# 3_Interface1.net
KiCad netlist of a schematic drawn in Altium Designer
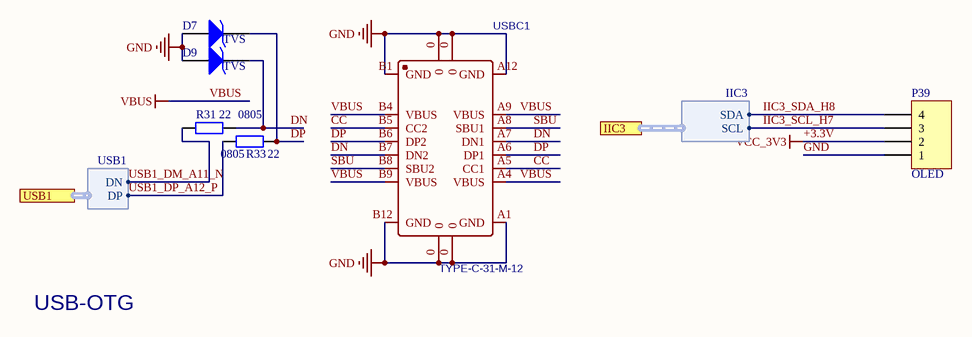
[diagram p0: 3.Interface1.SchDoc]

(export (version "E")
  (design (tool "Eeschema 10.0.6"))
  (components
    (comp (ref "D7")
      (value "TVS")
      (footprint "SOD-523")
      (description "High Conductance Fast Diode")
      (fields (field (name "PUBLISHER") "Altium Limited"))
      (libsource (lib "QT") (part "D"))
    )
    (comp (ref "D9")
      (value "TVS")
      (footprint "SOD-523")
      (description "High Conductance Fast Diode")
      (fields (field (name "PUBLISHER") "Altium Limited"))
      (libsource (lib "QT") (part "D"))
    )
    (comp (ref "P39")
      (value "OLED")
      (footprint "HDR1X4")
      (description "Header, 4-Pin")
      (fields (field (name "PUBLISHER") "Altium Limited"))
      (libsource (lib "Miscellaneous Connectors") (part "Header 4"))
    )
    (comp (ref "R31")
      (value "0805")
      (footprint "R 0805_L")
      (description "Resistor")
      (fields (field (name "ALTIUM_VALUE") "22") (field (name "PUBLISHER") "Altium Limited"))
      (libsource (lib "QT") (part "RES2"))
    )
    (comp (ref "R33")
      (value "0805")
      (footprint "R 0805_L")
      (description "Resistor")
      (fields (field (name "ALTIUM_VALUE") "22") (field (name "PUBLISHER") "Altium Limited"))
      (libsource (lib "QT") (part "RES2"))
    )
    (comp (ref "USBC1")
      (value "TYPE-C-31-M-12")
      (footprint "TYPE-C-USB-17")
      (libsource (lib "Interface") (part "TYPE-C-31-M-12"))
    )
  )
  (nets
    (net (code "3") (name "/CC") (class "Default")
      (node (ref "USBC1") (pin "A5") (pinfunction "CC1_A5") (pintype "passive"))
      (node (ref "USBC1") (pin "B5") (pinfunction "CC2_B5") (pintype "passive"))
    )
    (net (code "4") (name "/DN") (class "Default")
      (node (ref "D9") (pin "2") (pinfunction "K_2") (pintype "passive"))
      (node (ref "R31") (pin "2") (pinfunction "2_2") (pintype "passive"))
      (node (ref "USBC1") (pin "A7") (pinfunction "DN1_A7") (pintype "passive"))
      (node (ref "USBC1") (pin "B7") (pinfunction "DN2_B7") (pintype "passive"))
    )
    (net (code "5") (name "/DP") (class "Default")
      (node (ref "D7") (pin "2") (pinfunction "K_2") (pintype "passive"))
      (node (ref "R33") (pin "2") (pinfunction "2_2") (pintype "passive"))
      (node (ref "USBC1") (pin "A6") (pinfunction "DP1_A6") (pintype "passive"))
      (node (ref "USBC1") (pin "B6") (pinfunction "DP2_B6") (pintype "passive"))
    )
    (net (code "6") (name "/IIC3_SCL_H7") (class "Default")
      (node (ref "P39") (pin "3") (pinfunction "3_3") (pintype "passive"))
    )
    (net (code "7") (name "/IIC3_SDA_H8") (class "Default")
      (node (ref "P39") (pin "4") (pinfunction "4_4") (pintype "passive"))
    )
    (net (code "8") (name "/SBU") (class "Default")
      (node (ref "USBC1") (pin "A8") (pinfunction "SBU1_A8") (pintype "passive"))
      (node (ref "USBC1") (pin "B8") (pinfunction "SBU2_B8") (pintype "passive"))
    )
    (net (code "9") (name "/USB1_DM_A11_N") (class "Default")
      (node (ref "R31") (pin "1") (pinfunction "1_1") (pintype "passive"))
    )
    (net (code "10") (name "/USB1_DP_A12_P") (class "Default")
      (node (ref "R33") (pin "1") (pinfunction "1_1") (pintype "passive"))
    )
    (net (code "13") (name "GND") (class "Default")
      (node (ref "D7") (pin "1") (pinfunction "A_1") (pintype "passive"))
      (node (ref "D9") (pin "1") (pinfunction "A_1") (pintype "passive"))
      (node (ref "P39") (pin "1") (pinfunction "1_1") (pintype "passive"))
      (node (ref "USBC1") (pin "0") (pinfunction "0_0") (pintype "passive"))
      (node (ref "USBC1") (pin "A1") (pinfunction "GND_A1") (pintype "passive"))
      (node (ref "USBC1") (pin "A12") (pinfunction "GND_A12") (pintype "passive"))
      (node (ref "USBC1") (pin "B1") (pinfunction "GND_B1") (pintype "passive"))
      (node (ref "USBC1") (pin "B12") (pinfunction "GND_B12") (pintype "passive"))
    )
    (net (code "14") (name "VBUS") (class "Default")
      (node (ref "USBC1") (pin "A4") (pinfunction "VBUS_A4") (pintype "passive"))
      (node (ref "USBC1") (pin "A9") (pinfunction "VBUS_A9") (pintype "passive"))
      (node (ref "USBC1") (pin "B4") (pinfunction "VBUS_B4") (pintype "passive"))
      (node (ref "USBC1") (pin "B9") (pinfunction "VBUS_B9") (pintype "passive"))
    )
    (net (code "15") (name "VCC_3V3") (class "Default")
      (node (ref "P39") (pin "2") (pinfunction "2_2") (pintype "passive"))
    )
  )
)
